# raster_prototyp1.net
KiCad netlist of a schematic drawn in EAGLE
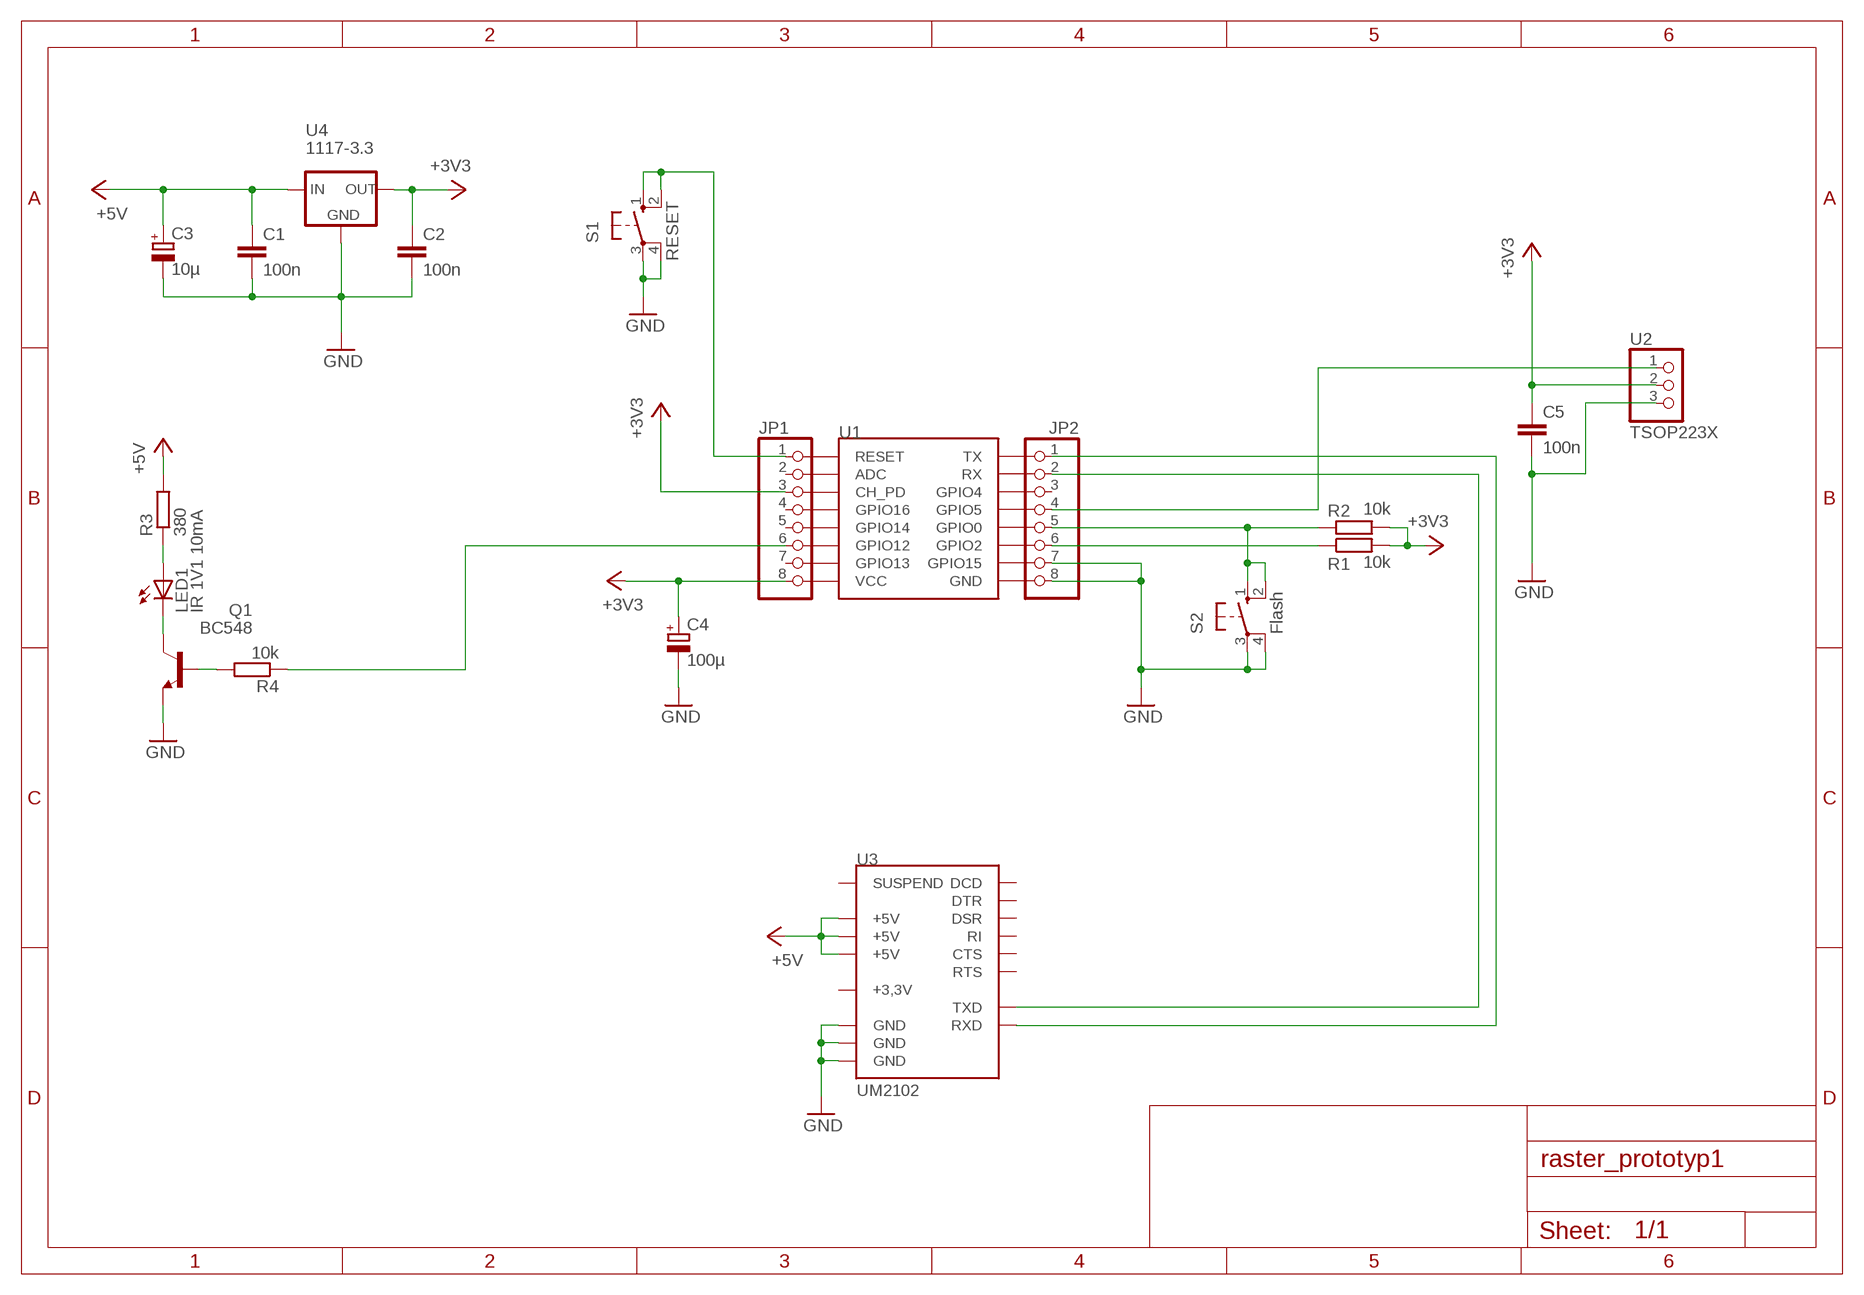
[diagram p0: schematic, sheet 1]

(export (version "E")
  (design (tool "Eeschema 10.0.6"))
  (components
    (comp (ref "C1")
      (value "100n")
      (footprint "eagle-import:C0805")
      (libsource (lib "eagle-import") (part "C-EUC0805"))
    )
    (comp (ref "C2")
      (value "100n")
      (footprint "eagle-import:C0805")
      (libsource (lib "eagle-import") (part "C-EUC0805"))
    )
    (comp (ref "C3")
      (value "10µ")
      (footprint "eagle-import:E2,5-5")
      (libsource (lib "eagle-import") (part "CPOL-EUE2.5-5"))
    )
    (comp (ref "C4")
      (value "100µ")
      (footprint "eagle-import:E2,5-7")
      (libsource (lib "eagle-import") (part "CPOL-EUE2.5-7"))
    )
    (comp (ref "C5")
      (value "100n")
      (footprint "eagle-import:C0805")
      (libsource (lib "eagle-import") (part "C-EUC0805"))
    )
    (comp (ref "JP1")
      (value "PINHD-1X8_2.54")
      (footprint "eagle-import:1X08")
      (libsource (lib "eagle-import") (part "PINHD-1X8_2.54"))
    )
    (comp (ref "JP2")
      (value "PINHD-1X8_2.54")
      (footprint "eagle-import:1X08")
      (libsource (lib "eagle-import") (part "PINHD-1X8_2.54"))
    )
    (comp (ref "LED1")
      (value "IR 1V1 10mA")
      (footprint "eagle-import:LED5MM")
      (libsource (lib "eagle-import") (part "LED5MM"))
    )
    (comp (ref "Q1")
      (value "BC548")
      (footprint "eagle-import:TO92-EBC")
      (libsource (lib "eagle-import") (part "BC548"))
    )
    (comp (ref "R1")
      (value "10k")
      (footprint "eagle-import:0207_10")
      (libsource (lib "eagle-import") (part "R-EU_0207/10"))
    )
    (comp (ref "R2")
      (value "10k")
      (footprint "eagle-import:0207_10")
      (libsource (lib "eagle-import") (part "R-EU_0207/10"))
    )
    (comp (ref "R3")
      (value "380")
      (footprint "eagle-import:0207_15")
      (libsource (lib "eagle-import") (part "R-EU_0207/15"))
    )
    (comp (ref "R4")
      (value "10k")
      (footprint "eagle-import:0207_10")
      (libsource (lib "eagle-import") (part "R-EU_0207/10"))
    )
    (comp (ref "S1")
      (value "10-XX")
      (footprint "eagle-import:B3F-10XX")
      (fields (field (name "MPN") "B3F-1000"))
      (libsource (lib "eagle-import") (part "10-XX"))
    )
    (comp (ref "S2")
      (value "10-XX")
      (footprint "eagle-import:B3F-10XX")
      (fields (field (name "MPN") "B3F-1000"))
      (libsource (lib "eagle-import") (part "10-XX"))
    )
    (comp (ref "U1")
      (value "ESP12SMD")
      (footprint "eagle-import:ESP12-SMD")
      (libsource (lib "eagle-import") (part "ESP12SMD"))
    )
    (comp (ref "U2")
      (value "TSOP223X")
      (footprint "eagle-import:1X03")
      (libsource (lib "eagle-import") (part "PINHD-1X3_2.54"))
    )
    (comp (ref "U3")
      (value "UM2102")
      (footprint "eagle-import:UM2102")
      (libsource (lib "eagle-import") (part "UM2102"))
    )
    (comp (ref "U4")
      (value "1117-3.3")
      (footprint "eagle-import:SOT223")
      (libsource (lib "eagle-import") (part "LM1117"))
    )
  )
  (nets
    (net (code "1") (name "+3V3") (class "Default")
      (node (ref "C2") (pin "1") (pinfunction "1_1") (pintype "passive"))
      (node (ref "C4") (pin "+") (pinfunction "+_+") (pintype "passive"))
      (node (ref "C5") (pin "1") (pinfunction "1_1") (pintype "passive"))
      (node (ref "JP1") (pin "3") (pinfunction "3_3") (pintype "passive"))
      (node (ref "JP1") (pin "8") (pinfunction "8_8") (pintype "passive"))
      (node (ref "R1") (pin "2") (pinfunction "2_2") (pintype "passive"))
      (node (ref "R2") (pin "2") (pinfunction "2_2") (pintype "passive"))
      (node (ref "U2") (pin "2") (pinfunction "2_2") (pintype "passive"))
      (node (ref "U4") (pin "2") (pinfunction "OUT_2") (pintype "passive"))
    )
    (net (code "2") (name "+5V") (class "Default")
      (node (ref "C1") (pin "1") (pinfunction "1_1") (pintype "passive"))
      (node (ref "C3") (pin "+") (pinfunction "+_+") (pintype "passive"))
      (node (ref "R3") (pin "2") (pinfunction "2_2") (pintype "passive"))
      (node (ref "U3") (pin "ST1-3") (pinfunction "+5V_ST1-3") (pintype "bidirectional"))
      (node (ref "U3") (pin "ST2-9") (pinfunction "+5V_ST2-9") (pintype "bidirectional"))
      (node (ref "U3") (pin "ST3-7") (pinfunction "+5V_ST3-7") (pintype "bidirectional"))
      (node (ref "U4") (pin "3") (pinfunction "IN_3") (pintype "input"))
    )
    (net (code "3") (name "/+3,3V") (class "Default")
      (node (ref "U3") (pin "ST2-11") (pinfunction "+3,3V_ST2-11") (pintype "power_in"))
    )
    (net (code "4") (name "GND") (class "Default")
      (node (ref "C1") (pin "2") (pinfunction "2_2") (pintype "passive"))
      (node (ref "C2") (pin "2") (pinfunction "2_2") (pintype "passive"))
      (node (ref "C3") (pin "-") (pinfunction "-_-") (pintype "passive"))
      (node (ref "C4") (pin "-") (pinfunction "-_-") (pintype "passive"))
      (node (ref "C5") (pin "2") (pinfunction "2_2") (pintype "passive"))
      (node (ref "JP2") (pin "7") (pinfunction "7_7") (pintype "passive"))
      (node (ref "JP2") (pin "8") (pinfunction "8_8") (pintype "passive"))
      (node (ref "Q1") (pin "E") (pinfunction "E_E") (pintype "passive"))
      (node (ref "S1") (pin "3") (pinfunction "P_3") (pintype "passive"))
      (node (ref "S1") (pin "4") (pinfunction "P1_4") (pintype "passive"))
      (node (ref "S2") (pin "3") (pinfunction "P_3") (pintype "passive"))
      (node (ref "S2") (pin "4") (pinfunction "P1_4") (pintype "passive"))
      (node (ref "U2") (pin "3") (pinfunction "3_3") (pintype "passive"))
      (node (ref "U3") (pin "ST1-1") (pinfunction "GND_ST1-1") (pintype "power_in"))
      (node (ref "U3") (pin "ST2-7") (pinfunction "GND_ST2-7") (pintype "power_in"))
      (node (ref "U3") (pin "ST3-9") (pinfunction "GND_ST3-9") (pintype "power_in"))
      (node (ref "U4") (pin "1") (pinfunction "GND_1") (pintype "input"))
    )
    (net (code "5") (name "Net-(JP1-Pad6)") (class "Default")
      (node (ref "JP1") (pin "6") (pinfunction "6_6") (pintype "passive"))
      (node (ref "R4") (pin "1") (pinfunction "1_1") (pintype "passive"))
    )
    (net (code "6") (name "Net-(JP2-Pad4)") (class "Default")
      (node (ref "JP2") (pin "4") (pinfunction "4_4") (pintype "passive"))
      (node (ref "U2") (pin "1") (pinfunction "1_1") (pintype "passive"))
    )
    (net (code "7") (name "Net-(JP2-Pad6)") (class "Default")
      (node (ref "JP2") (pin "6") (pinfunction "6_6") (pintype "passive"))
      (node (ref "R1") (pin "1") (pinfunction "1_1") (pintype "passive"))
    )
    (net (code "8") (name "Net-(LED1-C)") (class "Default")
      (node (ref "LED1") (pin "K") (pinfunction "C_K") (pintype "passive"))
      (node (ref "Q1") (pin "C") (pinfunction "C_C") (pintype "passive"))
    )
    (net (code "9") (name "Net-(LED1-PadA)") (class "Default")
      (node (ref "LED1") (pin "A") (pinfunction "A_A") (pintype "passive"))
      (node (ref "R3") (pin "1") (pinfunction "1_1") (pintype "passive"))
    )
    (net (code "10") (name "Net-(Q1-PadB)") (class "Default")
      (node (ref "Q1") (pin "B") (pinfunction "B_B") (pintype "passive"))
      (node (ref "R4") (pin "2") (pinfunction "2_2") (pintype "passive"))
    )
    (net (code "11") (name "Net-(S1-S)") (class "Default")
      (node (ref "JP1") (pin "1") (pinfunction "1_1") (pintype "passive"))
      (node (ref "S1") (pin "1") (pinfunction "S_1") (pintype "passive"))
      (node (ref "S1") (pin "2") (pinfunction "S1_2") (pintype "passive"))
    )
    (net (code "12") (name "Net-(S2-S)") (class "Default")
      (node (ref "JP2") (pin "5") (pinfunction "5_5") (pintype "passive"))
      (node (ref "R2") (pin "1") (pinfunction "1_1") (pintype "passive"))
      (node (ref "S2") (pin "1") (pinfunction "S_1") (pintype "passive"))
      (node (ref "S2") (pin "2") (pinfunction "S1_2") (pintype "passive"))
    )
    (net (code "13") (name "Net-(U3-RXD)") (class "Default")
      (node (ref "JP2") (pin "1") (pinfunction "1_1") (pintype "passive"))
      (node (ref "U3") (pin "ST2-5") (pinfunction "RXD_ST2-5") (pintype "bidirectional"))
    )
    (net (code "14") (name "Net-(U3-TXD)") (class "Default")
      (node (ref "JP2") (pin "2") (pinfunction "2_2") (pintype "passive"))
      (node (ref "U3") (pin "ST2-3") (pinfunction "TXD_ST2-3") (pintype "bidirectional"))
    )
    (net (code "15") (name "unconnected-(JP1-Pad2)") (class "Default")
      (node (ref "JP1") (pin "2") (pinfunction "2_2") (pintype "passive"))
    )
    (net (code "16") (name "unconnected-(JP1-Pad4)") (class "Default")
      (node (ref "JP1") (pin "4") (pinfunction "4_4") (pintype "passive"))
    )
    (net (code "17") (name "unconnected-(JP1-Pad5)") (class "Default")
      (node (ref "JP1") (pin "5") (pinfunction "5_5") (pintype "passive"))
    )
    (net (code "18") (name "unconnected-(JP1-Pad7)") (class "Default")
      (node (ref "JP1") (pin "7") (pinfunction "7_7") (pintype "passive"))
    )
    (net (code "19") (name "unconnected-(JP2-Pad3)") (class "Default")
      (node (ref "JP2") (pin "3") (pinfunction "3_3") (pintype "passive"))
    )
    (net (code "20") (name "unconnected-(U1-PadADC)") (class "Default")
      (node (ref "U1") (pin "ADC") (pinfunction "ADC_ADC") (pintype "bidirectional"))
    )
    (net (code "21") (name "unconnected-(U1-PadCH_PD)") (class "Default")
      (node (ref "U1") (pin "CH_PD") (pinfunction "CH_PD_CH_PD") (pintype "bidirectional"))
    )
    (net (code "22") (name "unconnected-(U1-PadGND)") (class "Default")
      (node (ref "U1") (pin "GND") (pinfunction "GND_GND") (pintype "bidirectional"))
    )
    (net (code "23") (name "unconnected-(U1-PadGPIO0)") (class "Default")
      (node (ref "U1") (pin "GPIO0") (pinfunction "GPIO0_GPIO0") (pintype "bidirectional"))
    )
    (net (code "24") (name "unconnected-(U1-PadGPIO2)") (class "Default")
      (node (ref "U1") (pin "GPIO2") (pinfunction "GPIO2_GPIO2") (pintype "bidirectional"))
    )
    (net (code "25") (name "unconnected-(U1-PadGPIO4)") (class "Default")
      (node (ref "U1") (pin "GPIO4") (pinfunction "GPIO4_GPIO4") (pintype "bidirectional"))
    )
    (net (code "26") (name "unconnected-(U1-PadGPIO5)") (class "Default")
      (node (ref "U1") (pin "GPIO5") (pinfunction "GPIO5_GPIO5") (pintype "bidirectional"))
    )
    (net (code "27") (name "unconnected-(U1-PadGPIO12)") (class "Default")
      (node (ref "U1") (pin "GPIO12") (pinfunction "GPIO12_GPIO12") (pintype "bidirectional"))
    )
    (net (code "28") (name "unconnected-(U1-PadGPIO13)") (class "Default")
      (node (ref "U1") (pin "GPIO13") (pinfunction "GPIO13_GPIO13") (pintype "bidirectional"))
    )
    (net (code "29") (name "unconnected-(U1-PadGPIO14)") (class "Default")
      (node (ref "U1") (pin "GPIO14") (pinfunction "GPIO14_GPIO14") (pintype "bidirectional"))
    )
    (net (code "30") (name "unconnected-(U1-PadGPIO15)") (class "Default")
      (node (ref "U1") (pin "GPIO15") (pinfunction "GPIO15_GPIO15") (pintype "bidirectional"))
    )
    (net (code "31") (name "unconnected-(U1-PadGPIO16)") (class "Default")
      (node (ref "U1") (pin "GPIO16") (pinfunction "GPIO16_GPIO16") (pintype "bidirectional"))
    )
    (net (code "32") (name "unconnected-(U1-PadRESET)") (class "Default")
      (node (ref "U1") (pin "RESET") (pinfunction "RESET_RESET") (pintype "bidirectional"))
    )
    (net (code "33") (name "unconnected-(U1-PadVCC)") (class "Default")
      (node (ref "U1") (pin "VCC") (pinfunction "VCC_VCC") (pintype "bidirectional"))
    )
    (net (code "34") (name "unconnected-(U1-RX-PadRXD0)") (class "Default")
      (node (ref "U1") (pin "RXD0") (pinfunction "RX_RXD0") (pintype "bidirectional"))
    )
    (net (code "35") (name "unconnected-(U1-TX-PadTXD0)") (class "Default")
      (node (ref "U1") (pin "TXD0") (pinfunction "TX_TXD0") (pintype "bidirectional"))
    )
    (net (code "36") (name "unconnected-(U3-CTS-PadST3-3)") (class "Default")
      (node (ref "U3") (pin "ST3-3") (pinfunction "CTS_ST3-3") (pintype "bidirectional"))
    )
    (net (code "37") (name "unconnected-(U3-DCD-PadST1-9)") (class "Default")
      (node (ref "U3") (pin "ST1-9") (pinfunction "DCD_ST1-9") (pintype "bidirectional"))
    )
    (net (code "38") (name "unconnected-(U3-DSR-PadST1-5)") (class "Default")
      (node (ref "U3") (pin "ST1-5") (pinfunction "DSR_ST1-5") (pintype "bidirectional"))
    )
    (net (code "39") (name "unconnected-(U3-DTR-PadST1-7)") (class "Default")
      (node (ref "U3") (pin "ST1-7") (pinfunction "DTR_ST1-7") (pintype "bidirectional"))
    )
    (net (code "40") (name "unconnected-(U3-RI-PadST2-1)") (class "Default")
      (node (ref "U3") (pin "ST2-1") (pinfunction "RI_ST2-1") (pintype "bidirectional"))
    )
    (net (code "41") (name "unconnected-(U3-RTS-PadST3-5)") (class "Default")
      (node (ref "U3") (pin "ST3-5") (pinfunction "RTS_ST3-5") (pintype "bidirectional"))
    )
    (net (code "42") (name "unconnected-(U3-SUSPEND-PadST3-1)") (class "Default")
      (node (ref "U3") (pin "ST3-1") (pinfunction "SUSPEND_ST3-1") (pintype "bidirectional"))
    )
  )
)
